# deska.net
KiCad netlist of a schematic drawn in EAGLE
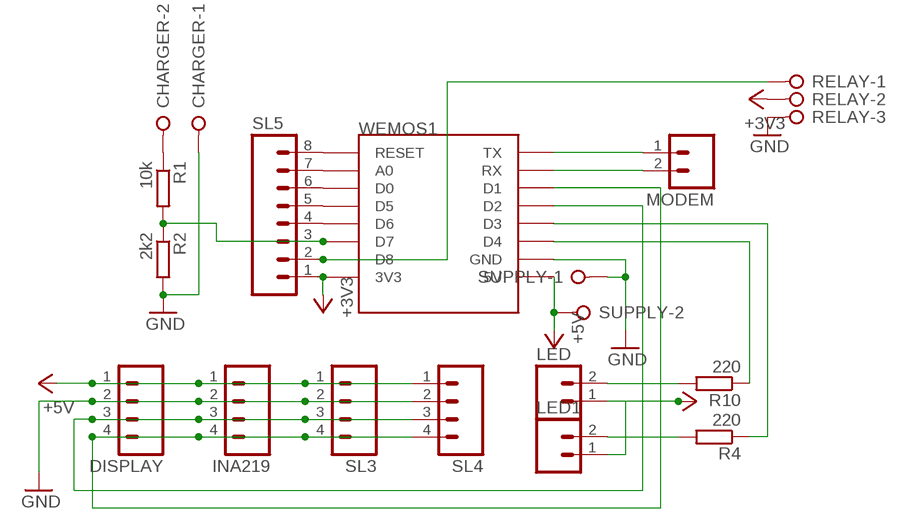
[diagram p0: schematic, sheet 1]

(export (version "E")
  (design (tool "Eeschema 10.0.6"))
  (components
    (comp (ref "CHARGER")
      (value "W237-02P")
      (footprint "eagle-import:W237-132")
      (libsource (lib "eagle-import") (part "W237-02P"))
    )
    (comp (ref "DISPLAY")
      (value "M04")
      (footprint "eagle-import:04P")
      (libsource (lib "eagle-import") (part "M04"))
    )
    (comp (ref "INA219")
      (value "M04")
      (footprint "eagle-import:04P")
      (libsource (lib "eagle-import") (part "M04"))
    )
    (comp (ref "LED")
      (value "M02")
      (footprint "eagle-import:02P")
      (libsource (lib "eagle-import") (part "M02"))
    )
    (comp (ref "LED1")
      (value "M02")
      (footprint "eagle-import:02P")
      (libsource (lib "eagle-import") (part "M02"))
    )
    (comp (ref "MODEM")
      (value "M02")
      (footprint "eagle-import:02P")
      (libsource (lib "eagle-import") (part "M02"))
    )
    (comp (ref "R1")
      (value "10k")
      (footprint "eagle-import:0207_10")
      (libsource (lib "eagle-import") (part "R-EU_0207/10"))
    )
    (comp (ref "R2")
      (value "2k2")
      (footprint "eagle-import:0207_10")
      (libsource (lib "eagle-import") (part "R-EU_0207/10"))
    )
    (comp (ref "R4")
      (value "220")
      (footprint "eagle-import:0207_10")
      (libsource (lib "eagle-import") (part "R-EU_0207/10"))
    )
    (comp (ref "R10")
      (value "220")
      (footprint "eagle-import:0207_10")
      (libsource (lib "eagle-import") (part "R-EU_0207/10"))
    )
    (comp (ref "RELAY")
      (value "W237-3E")
      (footprint "eagle-import:W237-3E")
      (libsource (lib "eagle-import") (part "W237-3E"))
    )
    (comp (ref "SL3")
      (value "M04")
      (footprint "eagle-import:04P")
      (libsource (lib "eagle-import") (part "M04"))
    )
    (comp (ref "SL4")
      (value "M04")
      (footprint "eagle-import:04P")
      (libsource (lib "eagle-import") (part "M04"))
    )
    (comp (ref "SL5")
      (value "M08")
      (footprint "eagle-import:08P")
      (libsource (lib "eagle-import") (part "M08"))
    )
    (comp (ref "SUPPLY")
      (value "W237-02P")
      (footprint "eagle-import:W237-132")
      (libsource (lib "eagle-import") (part "W237-02P"))
    )
    (comp (ref "WEMOS1")
      (value "WEMOS-D1-MINI")
      (footprint "eagle-import:WEMOS-D1-MINI")
      (libsource (lib "eagle-import") (part "WEMOS-D1-MINI"))
    )
  )
  (nets
    (net (code "1") (name "+3V3") (class "Default")
      (node (ref "RELAY") (pin "2") (pinfunction "KL_2") (pintype "passive"))
      (node (ref "SL5") (pin "1") (pinfunction "1_1") (pintype "passive"))
      (node (ref "WEMOS1") (pin "3V3") (pinfunction "3V3_3V3") (pintype "bidirectional"))
    )
    (net (code "2") (name "+5V") (class "Default")
      (node (ref "DISPLAY") (pin "1") (pinfunction "1_1") (pintype "passive"))
      (node (ref "INA219") (pin "1") (pinfunction "1_1") (pintype "passive"))
      (node (ref "LED") (pin "1") (pinfunction "1_1") (pintype "passive"))
      (node (ref "LED1") (pin "1") (pinfunction "1_1") (pintype "passive"))
      (node (ref "SL3") (pin "1") (pinfunction "1_1") (pintype "passive"))
      (node (ref "SL4") (pin "1") (pinfunction "1_1") (pintype "passive"))
      (node (ref "SUPPLY") (pin "2") (pinfunction "KL_2") (pintype "passive"))
      (node (ref "WEMOS1") (pin "5V") (pinfunction "5V_5V") (pintype "bidirectional"))
    )
    (net (code "3") (name "GND") (class "Default")
      (node (ref "CHARGER") (pin "1") (pinfunction "KL_1") (pintype "passive"))
      (node (ref "DISPLAY") (pin "2") (pinfunction "2_2") (pintype "passive"))
      (node (ref "INA219") (pin "2") (pinfunction "2_2") (pintype "passive"))
      (node (ref "R2") (pin "2") (pinfunction "2_2") (pintype "passive"))
      (node (ref "RELAY") (pin "3") (pinfunction "KL_3") (pintype "passive"))
      (node (ref "SL3") (pin "2") (pinfunction "2_2") (pintype "passive"))
      (node (ref "SL4") (pin "2") (pinfunction "2_2") (pintype "passive"))
      (node (ref "SUPPLY") (pin "1") (pinfunction "KL_1") (pintype "passive"))
      (node (ref "WEMOS1") (pin "GND") (pinfunction "GND_GND") (pintype "bidirectional"))
    )
    (net (code "4") (name "Net-(CHARGERB-KL)") (class "Default")
      (node (ref "CHARGER") (pin "2") (pinfunction "KL_2") (pintype "passive"))
      (node (ref "R1") (pin "1") (pinfunction "1_1") (pintype "passive"))
    )
    (net (code "5") (name "Net-(DISPLAY-Pad3)") (class "Default")
      (node (ref "DISPLAY") (pin "3") (pinfunction "3_3") (pintype "passive"))
      (node (ref "INA219") (pin "3") (pinfunction "3_3") (pintype "passive"))
      (node (ref "SL3") (pin "3") (pinfunction "3_3") (pintype "passive"))
      (node (ref "SL4") (pin "3") (pinfunction "3_3") (pintype "passive"))
      (node (ref "WEMOS1") (pin "D2") (pinfunction "D2_D2") (pintype "bidirectional"))
    )
    (net (code "6") (name "Net-(DISPLAY-Pad4)") (class "Default")
      (node (ref "DISPLAY") (pin "4") (pinfunction "4_4") (pintype "passive"))
      (node (ref "INA219") (pin "4") (pinfunction "4_4") (pintype "passive"))
      (node (ref "SL3") (pin "4") (pinfunction "4_4") (pintype "passive"))
      (node (ref "SL4") (pin "4") (pinfunction "4_4") (pintype "passive"))
      (node (ref "WEMOS1") (pin "D1") (pinfunction "D1_D1") (pintype "bidirectional"))
    )
    (net (code "7") (name "Net-(LED-Pad2)") (class "Default")
      (node (ref "LED") (pin "2") (pinfunction "2_2") (pintype "passive"))
      (node (ref "R10") (pin "2") (pinfunction "2_2") (pintype "passive"))
    )
    (net (code "8") (name "Net-(LED1-Pad2)") (class "Default")
      (node (ref "LED1") (pin "2") (pinfunction "2_2") (pintype "passive"))
      (node (ref "R4") (pin "2") (pinfunction "2_2") (pintype "passive"))
    )
    (net (code "9") (name "Net-(MODEM-Pad1)") (class "Default")
      (node (ref "MODEM") (pin "1") (pinfunction "1_1") (pintype "passive"))
      (node (ref "WEMOS1") (pin "TX") (pinfunction "TX_TX") (pintype "bidirectional"))
    )
    (net (code "10") (name "Net-(MODEM-Pad2)") (class "Default")
      (node (ref "MODEM") (pin "2") (pinfunction "2_2") (pintype "passive"))
      (node (ref "WEMOS1") (pin "RX") (pinfunction "RX_RX") (pintype "bidirectional"))
    )
    (net (code "11") (name "Net-(R1-Pad2)") (class "Default")
      (node (ref "R1") (pin "2") (pinfunction "2_2") (pintype "passive"))
      (node (ref "R2") (pin "1") (pinfunction "1_1") (pintype "passive"))
      (node (ref "SL5") (pin "3") (pinfunction "3_3") (pintype "passive"))
      (node (ref "WEMOS1") (pin "D7") (pinfunction "D7_D7") (pintype "bidirectional"))
    )
    (net (code "12") (name "Net-(R4-Pad1)") (class "Default")
      (node (ref "R4") (pin "1") (pinfunction "1_1") (pintype "passive"))
      (node (ref "WEMOS1") (pin "D3") (pinfunction "D3_D3") (pintype "bidirectional"))
    )
    (net (code "13") (name "Net-(R10-Pad1)") (class "Default")
      (node (ref "R10") (pin "1") (pinfunction "1_1") (pintype "passive"))
      (node (ref "WEMOS1") (pin "D4") (pinfunction "D4_D4") (pintype "bidirectional"))
    )
    (net (code "14") (name "Net-(RELAYA-KL)") (class "Default")
      (node (ref "RELAY") (pin "1") (pinfunction "KL_1") (pintype "passive"))
      (node (ref "SL5") (pin "2") (pinfunction "2_2") (pintype "passive"))
      (node (ref "WEMOS1") (pin "D8") (pinfunction "D8_D8") (pintype "bidirectional"))
    )
    (net (code "15") (name "Net-(SL5-Pad4)") (class "Default")
      (node (ref "SL5") (pin "4") (pinfunction "4_4") (pintype "passive"))
      (node (ref "WEMOS1") (pin "D6") (pinfunction "D6_D6") (pintype "bidirectional"))
    )
    (net (code "16") (name "Net-(SL5-Pad5)") (class "Default")
      (node (ref "SL5") (pin "5") (pinfunction "5_5") (pintype "passive"))
      (node (ref "WEMOS1") (pin "D5") (pinfunction "D5_D5") (pintype "bidirectional"))
    )
    (net (code "17") (name "Net-(SL5-Pad6)") (class "Default")
      (node (ref "SL5") (pin "6") (pinfunction "6_6") (pintype "passive"))
      (node (ref "WEMOS1") (pin "D0") (pinfunction "D0_D0") (pintype "bidirectional"))
    )
    (net (code "18") (name "Net-(SL5-Pad7)") (class "Default")
      (node (ref "SL5") (pin "7") (pinfunction "7_7") (pintype "passive"))
      (node (ref "WEMOS1") (pin "A0") (pinfunction "A0_A0") (pintype "bidirectional"))
    )
    (net (code "19") (name "Net-(SL5-Pad8)") (class "Default")
      (node (ref "SL5") (pin "8") (pinfunction "8_8") (pintype "passive"))
      (node (ref "WEMOS1") (pin "RESET") (pinfunction "RESET_RESET") (pintype "bidirectional"))
    )
  )
)
